# narodmon-sch.net
KiCad netlist of a schematic drawn in EAGLE
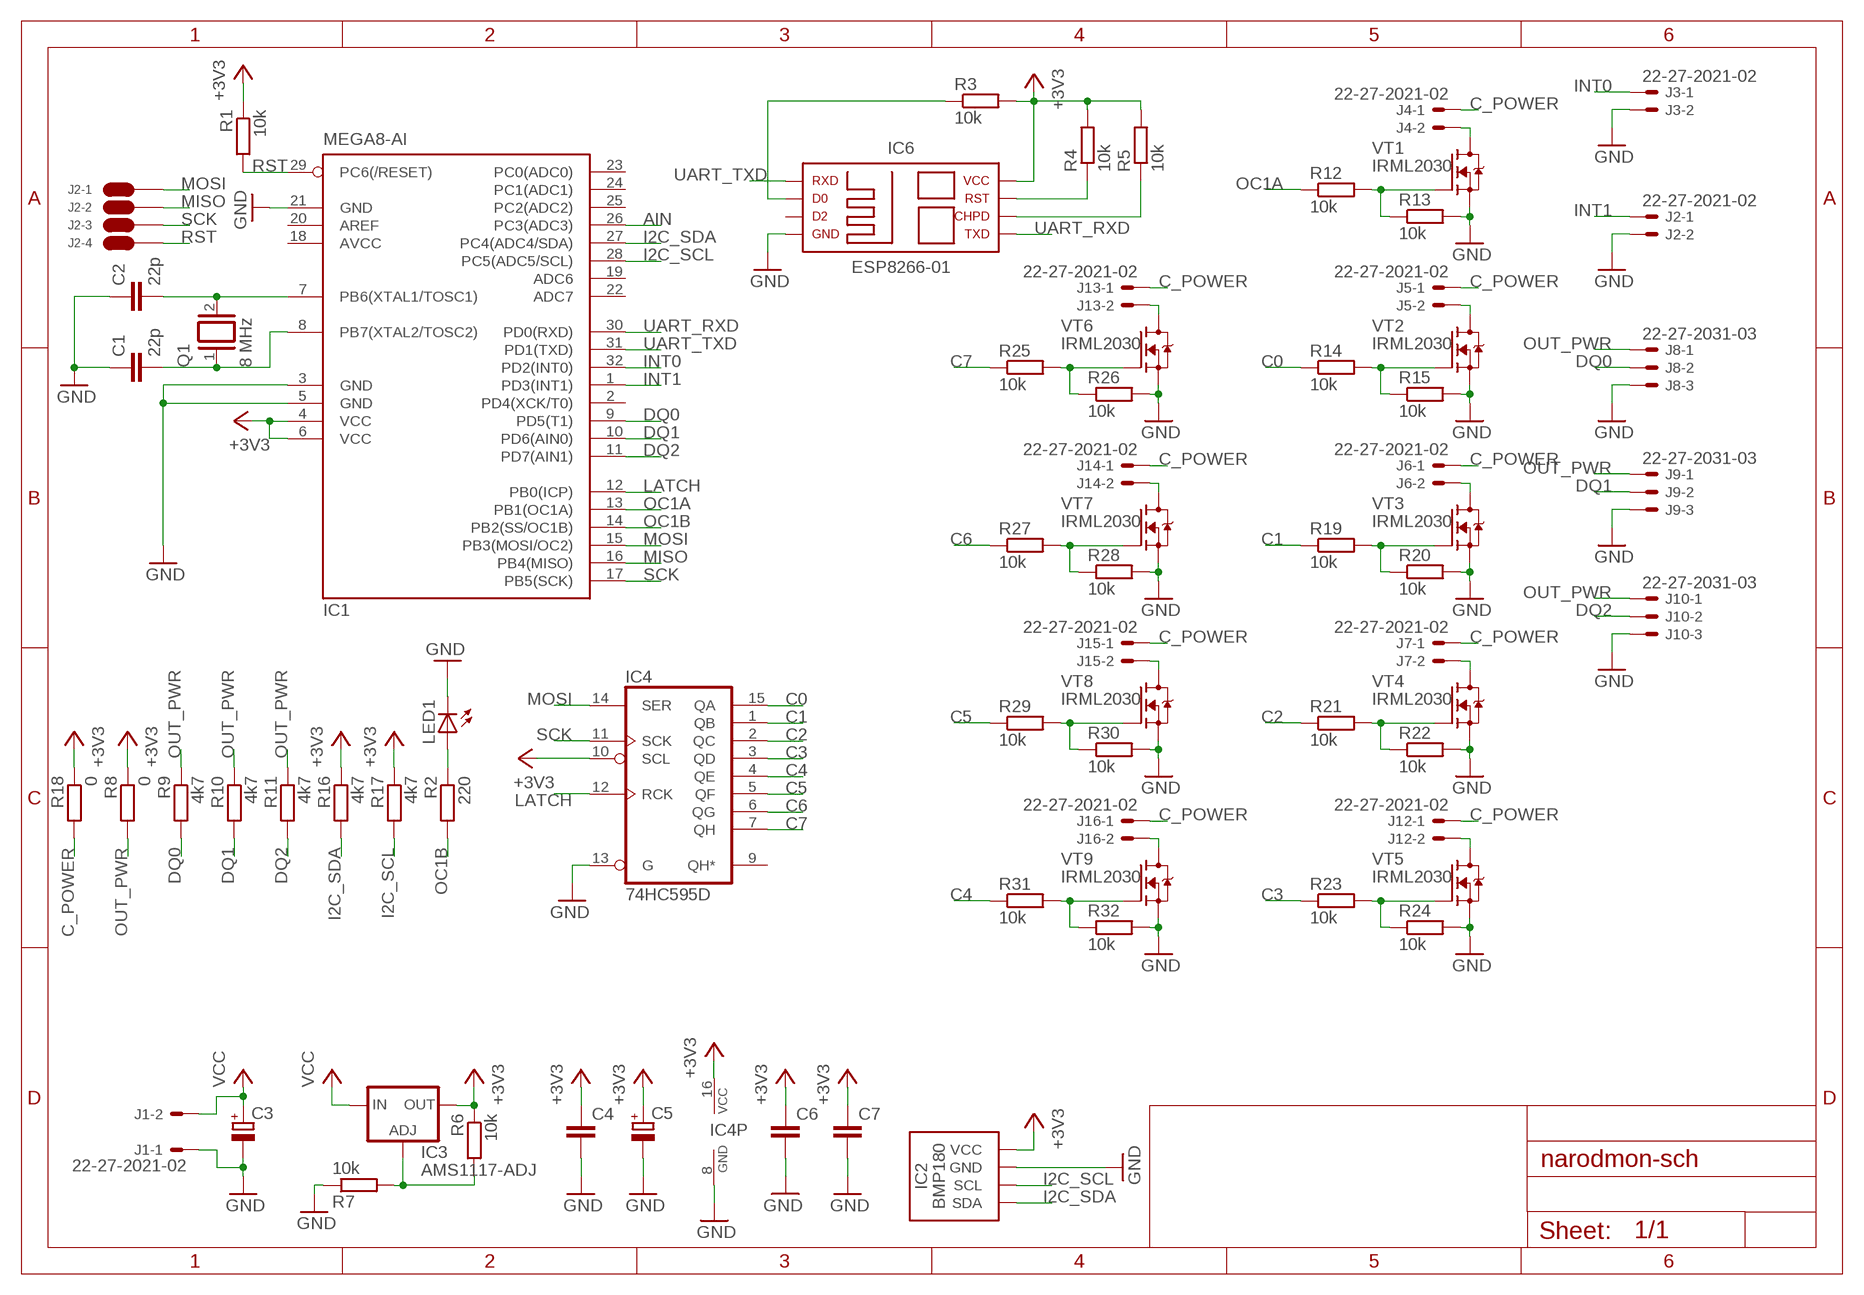
[diagram p0: schematic, sheet 1]

(export (version "E")
  (design (tool "Eeschema 10.0.6"))
  (components
    (comp (ref "C1")
      (value "22p")
      (footprint "eagle-import:C0603")
      (libsource (lib "eagle-import") (part "C-EUC0603"))
    )
    (comp (ref "C2")
      (value "22p")
      (footprint "eagle-import:C0603")
      (libsource (lib "eagle-import") (part "C-EUC0603"))
    )
    (comp (ref "C3")
      (value "CPOL-EUE3.5-10")
      (footprint "eagle-import:E3,5-10")
      (libsource (lib "eagle-import") (part "CPOL-EUE3.5-10"))
    )
    (comp (ref "C4")
      (value "C-EUC0805")
      (footprint "eagle-import:C0805")
      (libsource (lib "eagle-import") (part "C-EUC0805"))
    )
    (comp (ref "C5")
      (value "CPOL-EUE2.5-7")
      (footprint "eagle-import:E2,5-7")
      (libsource (lib "eagle-import") (part "CPOL-EUE2.5-7"))
    )
    (comp (ref "C6")
      (value "C-EUC0805")
      (footprint "eagle-import:C0805")
      (libsource (lib "eagle-import") (part "C-EUC0805"))
    )
    (comp (ref "C7")
      (value "C-EUC0805")
      (footprint "eagle-import:C0805")
      (libsource (lib "eagle-import") (part "C-EUC0805"))
    )
    (comp (ref "IC1")
      (value "MEGA8-AI")
      (footprint "eagle-import:TQFP32-08")
      (fields (field (name "MPN") "ATMEGA8-16AU"))
      (libsource (lib "eagle-import") (part "MEGA8-AI"))
    )
    (comp (ref "IC2")
      (value "BMP180C")
      (footprint "eagle-import:BMP180-CHIP")
      (libsource (lib "eagle-import") (part "BMP180C"))
    )
    (comp (ref "IC3")
      (value "AMS1117-ADJ")
      (footprint "eagle-import:SOT223")
      (libsource (lib "eagle-import") (part "AMS1117-ADJ"))
    )
    (comp (ref "IC4")
      (value "74HC595D")
      (footprint "eagle-import:SO16")
      (libsource (lib "eagle-import") (part "74595DHC"))
    )
    (comp (ref "IC6")
      (value "ESP-01")
      (footprint "eagle-import:ESP-01")
      (libsource (lib "eagle-import") (part "ESP-01"))
    )
    (comp (ref "J1")
      (value "22-27-2021-02")
      (footprint "eagle-import:6410-02")
      (libsource (lib "eagle-import") (part "22-?-0227-2021"))
    )
    (comp (ref "J2")
      (value "22-27-2021-02")
      (footprint "eagle-import:6410-02")
      (libsource (lib "eagle-import") (part "22-?-0227-2021"))
    )
    (comp (ref "J2-1")
      (value "W1")
      (footprint "eagle-import:W1")
      (libsource (lib "eagle-import") (part "W1"))
    )
    (comp (ref "J2-2")
      (value "W1")
      (footprint "eagle-import:W1")
      (libsource (lib "eagle-import") (part "W1"))
    )
    (comp (ref "J2-3")
      (value "W1")
      (footprint "eagle-import:W1")
      (libsource (lib "eagle-import") (part "W1"))
    )
    (comp (ref "J2-4")
      (value "W1")
      (footprint "eagle-import:W1")
      (libsource (lib "eagle-import") (part "W1"))
    )
    (comp (ref "J3")
      (value "22-27-2021-02")
      (footprint "eagle-import:6410-02")
      (libsource (lib "eagle-import") (part "22-?-0227-2021"))
    )
    (comp (ref "J4")
      (value "22-27-2021-02")
      (footprint "eagle-import:6410-02")
      (libsource (lib "eagle-import") (part "22-?-0227-2021"))
    )
    (comp (ref "J5")
      (value "22-27-2021-02")
      (footprint "eagle-import:6410-02")
      (libsource (lib "eagle-import") (part "22-?-0227-2021"))
    )
    (comp (ref "J6")
      (value "22-27-2021-02")
      (footprint "eagle-import:6410-02")
      (libsource (lib "eagle-import") (part "22-?-0227-2021"))
    )
    (comp (ref "J7")
      (value "22-27-2021-02")
      (footprint "eagle-import:6410-02")
      (libsource (lib "eagle-import") (part "22-?-0227-2021"))
    )
    (comp (ref "J8")
      (value "22-27-2031-03")
      (footprint "eagle-import:6410-03")
      (libsource (lib "eagle-import") (part "22-?-0327-2031"))
    )
    (comp (ref "J9")
      (value "22-27-2031-03")
      (footprint "eagle-import:6410-03")
      (libsource (lib "eagle-import") (part "22-?-0327-2031"))
    )
    (comp (ref "J10")
      (value "22-27-2031-03")
      (footprint "eagle-import:6410-03")
      (libsource (lib "eagle-import") (part "22-?-0327-2031"))
    )
    (comp (ref "J12")
      (value "22-27-2021-02")
      (footprint "eagle-import:6410-02")
      (libsource (lib "eagle-import") (part "22-?-0227-2021"))
    )
    (comp (ref "J13")
      (value "22-27-2021-02")
      (footprint "eagle-import:6410-02")
      (libsource (lib "eagle-import") (part "22-?-0227-2021"))
    )
    (comp (ref "J14")
      (value "22-27-2021-02")
      (footprint "eagle-import:6410-02")
      (libsource (lib "eagle-import") (part "22-?-0227-2021"))
    )
    (comp (ref "J15")
      (value "22-27-2021-02")
      (footprint "eagle-import:6410-02")
      (libsource (lib "eagle-import") (part "22-?-0227-2021"))
    )
    (comp (ref "J16")
      (value "22-27-2021-02")
      (footprint "eagle-import:6410-02")
      (libsource (lib "eagle-import") (part "22-?-0227-2021"))
    )
    (comp (ref "LED1")
      (value "LED3MM")
      (footprint "eagle-import:LED3MM")
      (libsource (lib "eagle-import") (part "LED3MM"))
    )
    (comp (ref "Q1")
      (value "8 MHz")
      (footprint "eagle-import:QS")
      (libsource (lib "eagle-import") (part "XTAL/S"))
    )
    (comp (ref "R1")
      (value "10k")
      (footprint "eagle-import:R0603")
      (libsource (lib "eagle-import") (part "R-EU_R0603"))
    )
    (comp (ref "R2")
      (value "220")
      (footprint "eagle-import:R0603")
      (libsource (lib "eagle-import") (part "R-EU_R0603"))
    )
    (comp (ref "R3")
      (value "10k")
      (footprint "eagle-import:R0603")
      (libsource (lib "eagle-import") (part "R-EU_R0603"))
    )
    (comp (ref "R4")
      (value "10k")
      (footprint "eagle-import:R0603")
      (libsource (lib "eagle-import") (part "R-EU_R0603"))
    )
    (comp (ref "R5")
      (value "10k")
      (footprint "eagle-import:R0603")
      (libsource (lib "eagle-import") (part "R-EU_R0603"))
    )
    (comp (ref "R6")
      (value "10k")
      (footprint "eagle-import:R0603")
      (libsource (lib "eagle-import") (part "R-EU_R0603"))
    )
    (comp (ref "R7")
      (value "10k")
      (footprint "eagle-import:R0603")
      (libsource (lib "eagle-import") (part "R-EU_R0603"))
    )
    (comp (ref "R8")
      (value "0")
      (footprint "eagle-import:R1206")
      (libsource (lib "eagle-import") (part "R-EU_R1206"))
    )
    (comp (ref "R9")
      (value "4k7")
      (footprint "eagle-import:R0603")
      (libsource (lib "eagle-import") (part "R-EU_R0603"))
    )
    (comp (ref "R10")
      (value "4k7")
      (footprint "eagle-import:R0603")
      (libsource (lib "eagle-import") (part "R-EU_R0603"))
    )
    (comp (ref "R11")
      (value "4k7")
      (footprint "eagle-import:R0603")
      (libsource (lib "eagle-import") (part "R-EU_R0603"))
    )
    (comp (ref "R12")
      (value "10k")
      (footprint "eagle-import:R0603")
      (libsource (lib "eagle-import") (part "R-EU_R0603"))
    )
    (comp (ref "R13")
      (value "10k")
      (footprint "eagle-import:R0603")
      (libsource (lib "eagle-import") (part "R-EU_R0603"))
    )
    (comp (ref "R14")
      (value "10k")
      (footprint "eagle-import:R0603")
      (libsource (lib "eagle-import") (part "R-EU_R0603"))
    )
    (comp (ref "R15")
      (value "10k")
      (footprint "eagle-import:R0603")
      (libsource (lib "eagle-import") (part "R-EU_R0603"))
    )
    (comp (ref "R16")
      (value "4k7")
      (footprint "eagle-import:R0603")
      (libsource (lib "eagle-import") (part "R-EU_R0603"))
    )
    (comp (ref "R17")
      (value "4k7")
      (footprint "eagle-import:R0603")
      (libsource (lib "eagle-import") (part "R-EU_R0603"))
    )
    (comp (ref "R18")
      (value "0")
      (footprint "eagle-import:0204_7")
      (libsource (lib "eagle-import") (part "R-EU_0204/7"))
    )
    (comp (ref "R19")
      (value "10k")
      (footprint "eagle-import:R0603")
      (libsource (lib "eagle-import") (part "R-EU_R0603"))
    )
    (comp (ref "R20")
      (value "10k")
      (footprint "eagle-import:R0603")
      (libsource (lib "eagle-import") (part "R-EU_R0603"))
    )
    (comp (ref "R21")
      (value "10k")
      (footprint "eagle-import:R0603")
      (libsource (lib "eagle-import") (part "R-EU_R0603"))
    )
    (comp (ref "R22")
      (value "10k")
      (footprint "eagle-import:R0603")
      (libsource (lib "eagle-import") (part "R-EU_R0603"))
    )
    (comp (ref "R23")
      (value "10k")
      (footprint "eagle-import:R0603")
      (libsource (lib "eagle-import") (part "R-EU_R0603"))
    )
    (comp (ref "R24")
      (value "10k")
      (footprint "eagle-import:R0603")
      (libsource (lib "eagle-import") (part "R-EU_R0603"))
    )
    (comp (ref "R25")
      (value "10k")
      (footprint "eagle-import:R0603")
      (libsource (lib "eagle-import") (part "R-EU_R0603"))
    )
    (comp (ref "R26")
      (value "10k")
      (footprint "eagle-import:R0603")
      (libsource (lib "eagle-import") (part "R-EU_R0603"))
    )
    (comp (ref "R27")
      (value "10k")
      (footprint "eagle-import:R0603")
      (libsource (lib "eagle-import") (part "R-EU_R0603"))
    )
    (comp (ref "R28")
      (value "10k")
      (footprint "eagle-import:R0603")
      (libsource (lib "eagle-import") (part "R-EU_R0603"))
    )
    (comp (ref "R29")
      (value "10k")
      (footprint "eagle-import:R0603")
      (libsource (lib "eagle-import") (part "R-EU_R0603"))
    )
    (comp (ref "R30")
      (value "10k")
      (footprint "eagle-import:R0603")
      (libsource (lib "eagle-import") (part "R-EU_R0603"))
    )
    (comp (ref "R31")
      (value "10k")
      (footprint "eagle-import:R0603")
      (libsource (lib "eagle-import") (part "R-EU_R0603"))
    )
    (comp (ref "R32")
      (value "10k")
      (footprint "eagle-import:R0603")
      (libsource (lib "eagle-import") (part "R-EU_R0603"))
    )
    (comp (ref "VT1")
      (value "IRML2030")
      (footprint "eagle-import:SOT23")
      (libsource (lib "eagle-import") (part "IRML2030"))
    )
    (comp (ref "VT2")
      (value "IRML2030")
      (footprint "eagle-import:SOT23")
      (libsource (lib "eagle-import") (part "IRML2030"))
    )
    (comp (ref "VT3")
      (value "IRML2030")
      (footprint "eagle-import:SOT23")
      (libsource (lib "eagle-import") (part "IRML2030"))
    )
    (comp (ref "VT4")
      (value "IRML2030")
      (footprint "eagle-import:SOT23")
      (libsource (lib "eagle-import") (part "IRML2030"))
    )
    (comp (ref "VT5")
      (value "IRML2030")
      (footprint "eagle-import:SOT23")
      (libsource (lib "eagle-import") (part "IRML2030"))
    )
    (comp (ref "VT6")
      (value "IRML2030")
      (footprint "eagle-import:SOT23")
      (libsource (lib "eagle-import") (part "IRML2030"))
    )
    (comp (ref "VT7")
      (value "IRML2030")
      (footprint "eagle-import:SOT23")
      (libsource (lib "eagle-import") (part "IRML2030"))
    )
    (comp (ref "VT8")
      (value "IRML2030")
      (footprint "eagle-import:SOT23")
      (libsource (lib "eagle-import") (part "IRML2030"))
    )
    (comp (ref "VT9")
      (value "IRML2030")
      (footprint "eagle-import:SOT23")
      (libsource (lib "eagle-import") (part "IRML2030"))
    )
  )
  (nets
    (net (code "1") (name "+3V3") (class "Default")
      (node (ref "C4") (pin "1") (pinfunction "1_1") (pintype "passive"))
      (node (ref "C5") (pin "+") (pinfunction "+_+") (pintype "passive"))
      (node (ref "C6") (pin "1") (pinfunction "1_1") (pintype "passive"))
      (node (ref "C7") (pin "1") (pinfunction "1_1") (pintype "passive"))
      (node (ref "IC1") (pin "4") (pinfunction "VCC_4") (pintype "power_in"))
      (node (ref "IC1") (pin "6") (pinfunction "VCC_6") (pintype "power_in"))
      (node (ref "IC2") (pin "P$2") (pinfunction "VCC_P$2") (pintype "bidirectional"))
      (node (ref "IC2") (pin "P$3") (pinfunction "VCC_P$3") (pintype "bidirectional"))
      (node (ref "IC3") (pin "2") (pinfunction "OUT_2") (pintype "passive"))
      (node (ref "IC3") (pin "4") (pinfunction "OUT_4") (pintype "passive"))
      (node (ref "IC4") (pin "10") (pinfunction "SCL_10") (pintype "input"))
      (node (ref "IC4") (pin "16") (pinfunction "VCC_16") (pintype "power_in"))
      (node (ref "IC6") (pin "VCC") (pinfunction "VCC_VCC") (pintype "bidirectional"))
      (node (ref "R1") (pin "1") (pinfunction "1_1") (pintype "passive"))
      (node (ref "R16") (pin "1") (pinfunction "1_1") (pintype "passive"))
      (node (ref "R17") (pin "1") (pinfunction "1_1") (pintype "passive"))
      (node (ref "R18") (pin "1") (pinfunction "1_1") (pintype "passive"))
      (node (ref "R3") (pin "2") (pinfunction "2_2") (pintype "passive"))
      (node (ref "R4") (pin "2") (pinfunction "2_2") (pintype "passive"))
      (node (ref "R5") (pin "2") (pinfunction "2_2") (pintype "passive"))
      (node (ref "R6") (pin "1") (pinfunction "1_1") (pintype "passive"))
      (node (ref "R8") (pin "1") (pinfunction "1_1") (pintype "passive"))
    )
    (net (code "2") (name "/AIN") (class "Default")
      (node (ref "IC1") (pin "26") (pinfunction "PC3(ADC3)_26") (pintype "bidirectional"))
    )
    (net (code "3") (name "/AVCC") (class "Default")
      (node (ref "IC1") (pin "18") (pinfunction "AVCC_18") (pintype "power_in"))
    )
    (net (code "4") (name "/C0") (class "Default")
      (node (ref "IC4") (pin "15") (pinfunction "QA_15") (pintype "tri_state"))
      (node (ref "R14") (pin "1") (pinfunction "1_1") (pintype "passive"))
    )
    (net (code "5") (name "/C1") (class "Default")
      (node (ref "IC4") (pin "1") (pinfunction "QB_1") (pintype "tri_state"))
      (node (ref "R19") (pin "1") (pinfunction "1_1") (pintype "passive"))
    )
    (net (code "6") (name "/C2") (class "Default")
      (node (ref "IC4") (pin "2") (pinfunction "QC_2") (pintype "tri_state"))
      (node (ref "R21") (pin "1") (pinfunction "1_1") (pintype "passive"))
    )
    (net (code "7") (name "/C3") (class "Default")
      (node (ref "IC4") (pin "3") (pinfunction "QD_3") (pintype "tri_state"))
      (node (ref "R23") (pin "1") (pinfunction "1_1") (pintype "passive"))
    )
    (net (code "8") (name "/C4") (class "Default")
      (node (ref "IC4") (pin "4") (pinfunction "QE_4") (pintype "tri_state"))
      (node (ref "R31") (pin "1") (pinfunction "1_1") (pintype "passive"))
    )
    (net (code "9") (name "/C5") (class "Default")
      (node (ref "IC4") (pin "5") (pinfunction "QF_5") (pintype "tri_state"))
      (node (ref "R29") (pin "1") (pinfunction "1_1") (pintype "passive"))
    )
    (net (code "10") (name "/C6") (class "Default")
      (node (ref "IC4") (pin "6") (pinfunction "QG_6") (pintype "tri_state"))
      (node (ref "R27") (pin "1") (pinfunction "1_1") (pintype "passive"))
    )
    (net (code "11") (name "/C7") (class "Default")
      (node (ref "IC4") (pin "7") (pinfunction "QH_7") (pintype "tri_state"))
      (node (ref "R25") (pin "1") (pinfunction "1_1") (pintype "passive"))
    )
    (net (code "12") (name "/C_POWER") (class "Default")
      (node (ref "J12") (pin "1") (pinfunction "S_1") (pintype "passive"))
      (node (ref "J13") (pin "1") (pinfunction "S_1") (pintype "passive"))
      (node (ref "J14") (pin "1") (pinfunction "S_1") (pintype "passive"))
      (node (ref "J15") (pin "1") (pinfunction "S_1") (pintype "passive"))
      (node (ref "J16") (pin "1") (pinfunction "S_1") (pintype "passive"))
      (node (ref "J4") (pin "1") (pinfunction "S_1") (pintype "passive"))
      (node (ref "J5") (pin "1") (pinfunction "S_1") (pintype "passive"))
      (node (ref "J6") (pin "1") (pinfunction "S_1") (pintype "passive"))
      (node (ref "J7") (pin "1") (pinfunction "S_1") (pintype "passive"))
      (node (ref "R18") (pin "2") (pinfunction "2_2") (pintype "passive"))
    )
    (net (code "13") (name "/DQ0") (class "Default")
      (node (ref "IC1") (pin "9") (pinfunction "PD5(T1)_9") (pintype "bidirectional"))
      (node (ref "J8") (pin "2") (pinfunction "S_2") (pintype "passive"))
      (node (ref "R9") (pin "2") (pinfunction "2_2") (pintype "passive"))
    )
    (net (code "14") (name "/DQ1") (class "Default")
      (node (ref "IC1") (pin "10") (pinfunction "PD6(AIN0)_10") (pintype "bidirectional"))
      (node (ref "J9") (pin "2") (pinfunction "S_2") (pintype "passive"))
      (node (ref "R10") (pin "2") (pinfunction "2_2") (pintype "passive"))
    )
    (net (code "15") (name "/DQ2") (class "Default")
      (node (ref "IC1") (pin "11") (pinfunction "PD7(AIN1)_11") (pintype "bidirectional"))
      (node (ref "J10") (pin "2") (pinfunction "S_2") (pintype "passive"))
      (node (ref "R11") (pin "2") (pinfunction "2_2") (pintype "passive"))
    )
    (net (code "16") (name "/I2C_SCL") (class "Default")
      (node (ref "IC1") (pin "28") (pinfunction "PC5(ADC5/SCL)_28") (pintype "bidirectional"))
      (node (ref "IC2") (pin "P$5") (pinfunction "SCL_P$5") (pintype "bidirectional"))
      (node (ref "R17") (pin "2") (pinfunction "2_2") (pintype "passive"))
    )
    (net (code "17") (name "/I2C_SDA") (class "Default")
      (node (ref "IC1") (pin "27") (pinfunction "PC4(ADC4/SDA)_27") (pintype "bidirectional"))
      (node (ref "IC2") (pin "P$6") (pinfunction "SDA_P$6") (pintype "bidirectional"))
      (node (ref "R16") (pin "2") (pinfunction "2_2") (pintype "passive"))
    )
    (net (code "18") (name "/INT0") (class "Default")
      (node (ref "IC1") (pin "32") (pinfunction "PD2(INT0)_32") (pintype "bidirectional"))
      (node (ref "J3") (pin "1") (pinfunction "S_1") (pintype "passive"))
    )
    (net (code "19") (name "/INT1") (class "Default")
      (node (ref "IC1") (pin "1") (pinfunction "PD3(INT1)_1") (pintype "bidirectional"))
      (node (ref "J2") (pin "1") (pinfunction "S_1") (pintype "passive"))
    )
    (net (code "20") (name "/LATCH") (class "Default")
      (node (ref "IC1") (pin "12") (pinfunction "PB0(ICP)_12") (pintype "bidirectional"))
      (node (ref "IC4") (pin "12") (pinfunction "RCK_12") (pintype "input"))
    )
    (net (code "21") (name "/MISO") (class "Default")
      (node (ref "IC1") (pin "16") (pinfunction "PB4(MISO)_16") (pintype "bidirectional"))
      (node (ref "J2-2") (pin "P$1") (pinfunction "P$1_P$1") (pintype "bidirectional"))
    )
    (net (code "22") (name "/MOSI") (class "Default")
      (node (ref "IC1") (pin "15") (pinfunction "PB3(MOSI/OC2)_15") (pintype "bidirectional"))
      (node (ref "IC4") (pin "14") (pinfunction "SER_14") (pintype "input"))
      (node (ref "J2-1") (pin "P$1") (pinfunction "P$1_P$1") (pintype "bidirectional"))
    )
    (net (code "23") (name "/OC1A") (class "Default")
      (node (ref "IC1") (pin "13") (pinfunction "PB1(OC1A)_13") (pintype "bidirectional"))
      (node (ref "R12") (pin "1") (pinfunction "1_1") (pintype "passive"))
    )
    (net (code "24") (name "/OC1B") (class "Default")
      (node (ref "IC1") (pin "14") (pinfunction "PB2(SS/OC1B)_14") (pintype "bidirectional"))
      (node (ref "R2") (pin "2") (pinfunction "2_2") (pintype "passive"))
    )
    (net (code "25") (name "/OUT_PWR") (class "Default")
      (node (ref "J10") (pin "1") (pinfunction "S_1") (pintype "passive"))
      (node (ref "J8") (pin "1") (pinfunction "S_1") (pintype "passive"))
      (node (ref "J9") (pin "1") (pinfunction "S_1") (pintype "passive"))
      (node (ref "R10") (pin "1") (pinfunction "1_1") (pintype "passive"))
      (node (ref "R11") (pin "1") (pinfunction "1_1") (pintype "passive"))
      (node (ref "R8") (pin "2") (pinfunction "2_2") (pintype "passive"))
      (node (ref "R9") (pin "1") (pinfunction "1_1") (pintype "passive"))
    )
    (net (code "26") (name "/RST") (class "Default")
      (node (ref "IC1") (pin "29") (pinfunction "PC6(/RESET)_29") (pintype "bidirectional"))
      (node (ref "J2-4") (pin "P$1") (pinfunction "P$1_P$1") (pintype "bidirectional"))
      (node (ref "R1") (pin "2") (pinfunction "2_2") (pintype "passive"))
    )
    (net (code "27") (name "/SCK") (class "Default")
      (node (ref "IC1") (pin "17") (pinfunction "PB5(SCK)_17") (pintype "bidirectional"))
      (node (ref "IC4") (pin "11") (pinfunction "SCK_11") (pintype "input"))
      (node (ref "J2-3") (pin "P$1") (pinfunction "P$1_P$1") (pintype "bidirectional"))
    )
    (net (code "28") (name "/UART_RXD") (class "Default")
      (node (ref "IC1") (pin "30") (pinfunction "PD0(RXD)_30") (pintype "bidirectional"))
      (node (ref "IC6") (pin "TXD") (pinfunction "TXD_TXD") (pintype "bidirectional"))
    )
    (net (code "29") (name "/UART_TXD") (class "Default")
      (node (ref "IC1") (pin "31") (pinfunction "PD1(TXD)_31") (pintype "bidirectional"))
      (node (ref "IC6") (pin "RXC") (pinfunction "RXD_RXC") (pintype "bidirectional"))
    )
    (net (code "30") (name "GND") (class "Default")
      (node (ref "C1") (pin "1") (pinfunction "1_1") (pintype "passive"))
      (node (ref "C2") (pin "1") (pinfunction "1_1") (pintype "passive"))
      (node (ref "C3") (pin "-") (pinfunction "-_-") (pintype "passive"))
      (node (ref "C4") (pin "2") (pinfunction "2_2") (pintype "passive"))
      (node (ref "C5") (pin "-") (pinfunction "-_-") (pintype "passive"))
      (node (ref "C6") (pin "2") (pinfunction "2_2") (pintype "passive"))
      (node (ref "C7") (pin "2") (pinfunction "2_2") (pintype "passive"))
      (node (ref "IC1") (pin "21") (pinfunction "GND_21") (pintype "power_in"))
      (node (ref "IC1") (pin "3") (pinfunction "GND_3") (pintype "power_in"))
      (node (ref "IC1") (pin "5") (pinfunction "GND_5") (pintype "power_in"))
      (node (ref "IC2") (pin "P$7") (pinfunction "GND_P$7") (pintype "bidirectional"))
      (node (ref "IC4") (pin "13") (pinfunction "G_13") (pintype "input"))
      (node (ref "IC4") (pin "8") (pinfunction "GND_8") (pintype "power_in"))
      (node (ref "IC6") (pin "GND") (pinfunction "GND_GND") (pintype "bidirectional"))
      (node (ref "J1") (pin "1") (pinfunction "S_1") (pintype "passive"))
      (node (ref "J10") (pin "3") (pinfunction "S_3") (pintype "passive"))
      (node (ref "J2") (pin "2") (pinfunction "S_2") (pintype "passive"))
      (node (ref "J3") (pin "2") (pinfunction "S_2") (pintype "passive"))
      (node (ref "J8") (pin "3") (pinfunction "S_3") (pintype "passive"))
      (node (ref "J9") (pin "3") (pinfunction "S_3") (pintype "passive"))
      (node (ref "LED1") (pin "K") (pinfunction "C_K") (pintype "passive"))
      (node (ref "R13") (pin "2") (pinfunction "2_2") (pintype "passive"))
      (node (ref "R15") (pin "2") (pinfunction "2_2") (pintype "passive"))
      (node (ref "R20") (pin "2") (pinfunction "2_2") (pintype "passive"))
      (node (ref "R22") (pin "2") (pinfunction "2_2") (pintype "passive"))
      (node (ref "R24") (pin "2") (pinfunction "2_2") (pintype "passive"))
      (node (ref "R26") (pin "2") (pinfunction "2_2") (pintype "passive"))
      (node (ref "R28") (pin "2") (pinfunction "2_2") (pintype "passive"))
      (node (ref "R30") (pin "2") (pinfunction "2_2") (pintype "passive"))
      (node (ref "R32") (pin "2") (pinfunction "2_2") (pintype "passive"))
      (node (ref "R7") (pin "1") (pinfunction "1_1") (pintype "passive"))
      (node (ref "VT1") (pin "2") (pinfunction "S_2") (pintype "passive"))
      (node (ref "VT2") (pin "2") (pinfunction "S_2") (pintype "passive"))
      (node (ref "VT3") (pin "2") (pinfunction "S_2") (pintype "passive"))
      (node (ref "VT4") (pin "2") (pinfunction "S_2") (pintype "passive"))
      (node (ref "VT5") (pin "2") (pinfunction "S_2") (pintype "passive"))
      (node (ref "VT6") (pin "2") (pinfunction "S_2") (pintype "passive"))
      (node (ref "VT7") (pin "2") (pinfunction "S_2") (pintype "passive"))
      (node (ref "VT8") (pin "2") (pinfunction "S_2") (pintype "passive"))
      (node (ref "VT9") (pin "2") (pinfunction "S_2") (pintype "passive"))
    )
    (net (code "31") (name "Net-(IC1-PB6(XTAL1{slash}TOSC1))") (class "Default")
      (node (ref "C2") (pin "2") (pinfunction "2_2") (pintype "passive"))
      (node (ref "IC1") (pin "7") (pinfunction "PB6(XTAL1/TOSC1)_7") (pintype "bidirectional"))
      (node (ref "Q1") (pin "2") (pinfunction "2_2") (pintype "passive"))
    )
    (net (code "32") (name "Net-(IC1-PB7(XTAL2{slash}TOSC2))") (class "Default")
      (node (ref "C1") (pin "2") (pinfunction "2_2") (pintype "passive"))
      (node (ref "IC1") (pin "8") (pinfunction "PB7(XTAL2/TOSC2)_8") (pintype "bidirectional"))
      (node (ref "Q1") (pin "1") (pinfunction "1_1") (pintype "passive"))
    )
    (net (code "33") (name "Net-(IC3-ADJ)") (class "Default")
      (node (ref "IC3") (pin "1") (pinfunction "ADJ_1") (pintype "input"))
      (node (ref "R6") (pin "2") (pinfunction "2_2") (pintype "passive"))
      (node (ref "R7") (pin "2") (pinfunction "2_2") (pintype "passive"))
    )
    (net (code "34") (name "Net-(IC6-PadCH_PD)") (class "Default")
      (node (ref "IC6") (pin "CH_PD") (pinfunction "CH_PD_CH_PD") (pintype "bidirectional"))
      (node (ref "R5") (pin "1") (pinfunction "1_1") (pintype "passive"))
    )
    (net (code "35") (name "Net-(IC6-PadGPIO0)") (class "Default")
      (node (ref "IC6") (pin "GPIO0") (pinfunction "GPIO0_GPIO0") (pintype "bidirectional"))
      (node (ref "R3") (pin "1") (pinfunction "1_1") (pintype "passive"))
    )
    (net (code "36") (name "Net-(IC6-PadRST)") (class "Default")
      (node (ref "IC6") (pin "RST") (pinfunction "RST_RST") (pintype "bidirectional"))
      (node (ref "R4") (pin "1") (pinfunction "1_1") (pintype "passive"))
    )
    (net (code "37") (name "Net-(J4B-S)") (class "Default")
      (node (ref "J4") (pin "2") (pinfunction "S_2") (pintype "passive"))
      (node (ref "VT1") (pin "3") (pinfunction "D_3") (pintype "passive"))
    )
    (net (code "38") (name "Net-(J5B-S)") (class "Default")
      (node (ref "J5") (pin "2") (pinfunction "S_2") (pintype "passive"))
      (node (ref "VT2") (pin "3") (pinfunction "D_3") (pintype "passive"))
    )
    (net (code "39") (name "Net-(J6B-S)") (class "Default")
      (node (ref "J6") (pin "2") (pinfunction "S_2") (pintype "passive"))
      (node (ref "VT3") (pin "3") (pinfunction "D_3") (pintype "passive"))
    )
    (net (code "40") (name "Net-(J7B-S)") (class "Default")
      (node (ref "J7") (pin "2") (pinfunction "S_2") (pintype "passive"))
      (node (ref "VT4") (pin "3") (pinfunction "D_3") (pintype "passive"))
    )
    (net (code "41") (name "Net-(J12B-S)") (class "Default")
      (node (ref "J12") (pin "2") (pinfunction "S_2") (pintype "passive"))
      (node (ref "VT5") (pin "3") (pinfunction "D_3") (pintype "passive"))
    )
    (net (code "42") (name "Net-(J13B-S)") (class "Default")
      (node (ref "J13") (pin "2") (pinfunction "S_2") (pintype "passive"))
      (node (ref "VT6") (pin "3") (pinfunction "D_3") (pintype "passive"))
    )
    (net (code "43") (name "Net-(J14B-S)") (class "Default")
      (node (ref "J14") (pin "2") (pinfunction "S_2") (pintype "passive"))
      (node (ref "VT7") (pin "3") (pinfunction "D_3") (pintype "passive"))
    )
    (net (code "44") (name "Net-(J15B-S)") (class "Default")
      (node (ref "J15") (pin "2") (pinfunction "S_2") (pintype "passive"))
      (node (ref "VT8") (pin "3") (pinfunction "D_3") (pintype "passive"))
    )
    (net (code "45") (name "Net-(J16B-S)") (class "Default")
      (node (ref "J16") (pin "2") (pinfunction "S_2") (pintype "passive"))
      (node (ref "VT9") (pin "3") (pinfunction "D_3") (pintype "passive"))
    )
    (net (code "46") (name "Net-(LED1-PadA)") (class "Default")
      (node (ref "LED1") (pin "A") (pinfunction "A_A") (pintype "passive"))
      (node (ref "R2") (pin "1") (pinfunction "1_1") (pintype "passive"))
    )
    (net (code "47") (name "Net-(VT1-G)") (class "Default")
      (node (ref "R12") (pin "2") (pinfunction "2_2") (pintype "passive"))
      (node (ref "R13") (pin "1") (pinfunction "1_1") (pintype "passive"))
      (node (ref "VT1") (pin "1") (pinfunction "G_1") (pintype "passive"))
    )
    (net (code "48") (name "Net-(VT2-G)") (class "Default")
      (node (ref "R14") (pin "2") (pinfunction "2_2") (pintype "passive"))
      (node (ref "R15") (pin "1") (pinfunction "1_1") (pintype "passive"))
      (node (ref "VT2") (pin "1") (pinfunction "G_1") (pintype "passive"))
    )
    (net (code "49") (name "Net-(VT3-G)") (class "Default")
      (node (ref "R19") (pin "2") (pinfunction "2_2") (pintype "passive"))
      (node (ref "R20") (pin "1") (pinfunction "1_1") (pintype "passive"))
      (node (ref "VT3") (pin "1") (pinfunction "G_1") (pintype "passive"))
    )
    (net (code "50") (name "Net-(VT4-G)") (class "Default")
      (node (ref "R21") (pin "2") (pinfunction "2_2") (pintype "passive"))
      (node (ref "R22") (pin "1") (pinfunction "1_1") (pintype "passive"))
      (node (ref "VT4") (pin "1") (pinfunction "G_1") (pintype "passive"))
    )
    (net (code "51") (name "Net-(VT5-G)") (class "Default")
      (node (ref "R23") (pin "2") (pinfunction "2_2") (pintype "passive"))
      (node (ref "R24") (pin "1") (pinfunction "1_1") (pintype "passive"))
      (node (ref "VT5") (pin "1") (pinfunction "G_1") (pintype "passive"))
    )
    (net (code "52") (name "Net-(VT6-G)") (class "Default")
      (node (ref "R25") (pin "2") (pinfunction "2_2") (pintype "passive"))
      (node (ref "R26") (pin "1") (pinfunction "1_1") (pintype "passive"))
      (node (ref "VT6") (pin "1") (pinfunction "G_1") (pintype "passive"))
    )
    (net (code "53") (name "Net-(VT7-G)") (class "Default")
      (node (ref "R27") (pin "2") (pinfunction "2_2") (pintype "passive"))
      (node (ref "R28") (pin "1") (pinfunction "1_1") (pintype "passive"))
      (node (ref "VT7") (pin "1") (pinfunction "G_1") (pintype "passive"))
    )
    (net (code "54") (name "Net-(VT8-G)") (class "Default")
      (node (ref "R29") (pin "2") (pinfunction "2_2") (pintype "passive"))
      (node (ref "R30") (pin "1") (pinfunction "1_1") (pintype "passive"))
      (node (ref "VT8") (pin "1") (pinfunction "G_1") (pintype "passive"))
    )
    (net (code "55") (name "Net-(VT9-G)") (class "Default")
      (node (ref "R31") (pin "2") (pinfunction "2_2") (pintype "passive"))
      (node (ref "R32") (pin "1") (pinfunction "1_1") (pintype "passive"))
      (node (ref "VT9") (pin "1") (pinfunction "G_1") (pintype "passive"))
    )
    (net (code "56") (name "VCC") (class "Default")
      (node (ref "C3") (pin "+") (pinfunction "+_+") (pintype "passive"))
      (node (ref "IC3") (pin "3") (pinfunction "IN_3") (pintype "input"))
      (node (ref "J1") (pin "2") (pinfunction "S_2") (pintype "passive"))
    )
    (net (code "57") (name "unconnected-(IC1-ADC6-Pad19)") (class "Default")
      (node (ref "IC1") (pin "19") (pinfunction "ADC6_19") (pintype "bidirectional"))
    )
    (net (code "58") (name "unconnected-(IC1-ADC7-Pad22)") (class "Default")
      (node (ref "IC1") (pin "22") (pinfunction "ADC7_22") (pintype "bidirectional"))
    )
    (net (code "59") (name "unconnected-(IC1-AREF-Pad20)") (class "Default")
      (node (ref "IC1") (pin "20") (pinfunction "AREF_20") (pintype "passive"))
    )
    (net (code "60") (name "unconnected-(IC1-PC0(ADC0)-Pad23)") (class "Default")
      (node (ref "IC1") (pin "23") (pinfunction "PC0(ADC0)_23") (pintype "bidirectional"))
    )
    (net (code "61") (name "unconnected-(IC1-PC1(ADC1)-Pad24)") (class "Default")
      (node (ref "IC1") (pin "24") (pinfunction "PC1(ADC1)_24") (pintype "bidirectional"))
    )
    (net (code "62") (name "unconnected-(IC1-PC2(ADC2)-Pad25)") (class "Default")
      (node (ref "IC1") (pin "25") (pinfunction "PC2(ADC2)_25") (pintype "bidirectional"))
    )
    (net (code "63") (name "unconnected-(IC1-PD4(XCK{slash}T0)-Pad2)") (class "Default")
      (node (ref "IC1") (pin "2") (pinfunction "PD4(XCK/T0)_2") (pintype "bidirectional"))
    )
    (net (code "64") (name "unconnected-(IC4A-QH*-Pad9)") (class "Default")
      (node (ref "IC4") (pin "9") (pinfunction "QH*_9") (pintype "tri_state"))
    )
    (net (code "65") (name "unconnected-(IC6-PadGPIO2)") (class "Default")
      (node (ref "IC6") (pin "GPIO2") (pinfunction "GPIO2_GPIO2") (pintype "bidirectional"))
    )
  )
)
